# 100pqfpBreakout.net
KiCad netlist of a schematic drawn in EAGLE
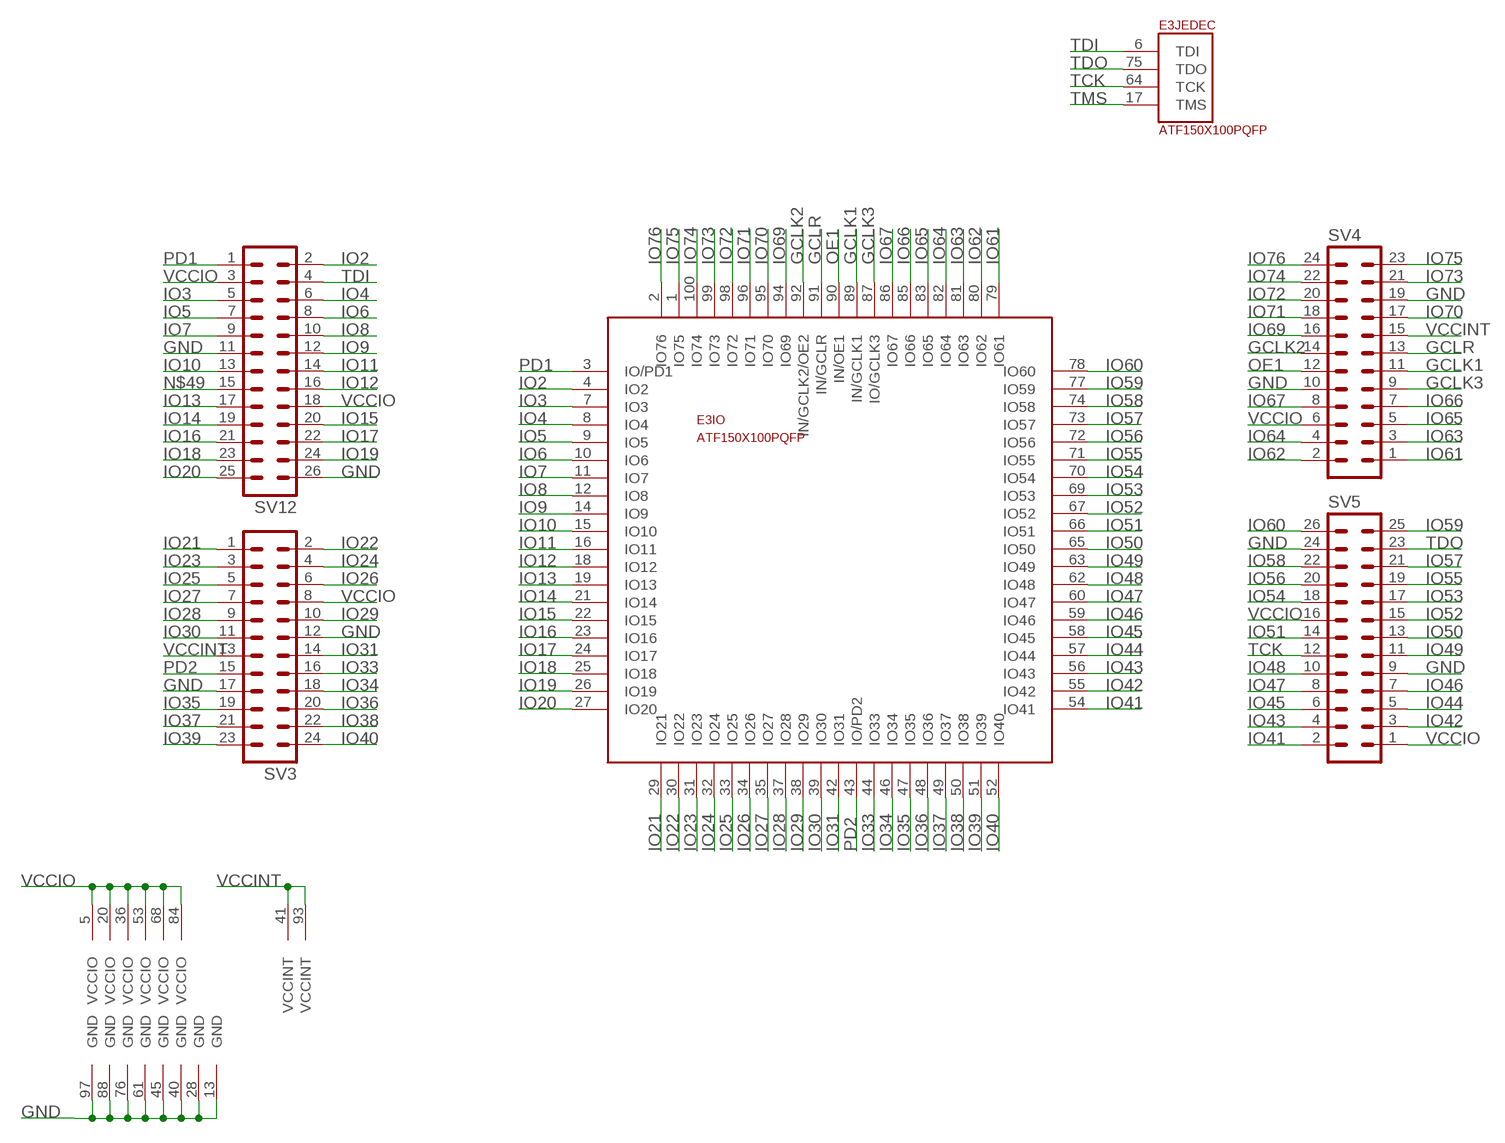
[diagram p0: schematic, sheet 1]

(export (version "E")
  (design (tool "Eeschema 10.0.6"))
  (components
    (comp (ref "E3")
      (value "ATF150X100PQFP")
      (footprint "eagle-import:PQFP-100")
      (libsource (lib "eagle-import") (part "ATF150X100PQFP"))
    )
    (comp (ref "SV3")
      (value "MA12-2")
      (footprint "eagle-import:MA12-2")
      (libsource (lib "eagle-import") (part "MA12-2"))
    )
    (comp (ref "SV4")
      (value "MA12-2")
      (footprint "eagle-import:MA12-2")
      (libsource (lib "eagle-import") (part "MA12-2"))
    )
    (comp (ref "SV5")
      (value "MA13-2")
      (footprint "eagle-import:MA13-2")
      (libsource (lib "eagle-import") (part "MA13-2"))
    )
    (comp (ref "SV12")
      (value "MA13-2")
      (footprint "eagle-import:MA13-2")
      (libsource (lib "eagle-import") (part "MA13-2"))
    )
  )
  (nets
    (net (code "1") (name "/GCLK1") (class "Default")
      (node (ref "E3") (pin "89") (pinfunction "IN/GCLK1_89") (pintype "input"))
      (node (ref "SV4") (pin "11") (pinfunction "11_11") (pintype "passive"))
    )
    (net (code "2") (name "/GCLK2") (class "Default")
      (node (ref "E3") (pin "92") (pinfunction "IN/GCLK2/OE2_92") (pintype "input"))
      (node (ref "SV4") (pin "14") (pinfunction "14_14") (pintype "passive"))
    )
    (net (code "3") (name "/GCLK3") (class "Default")
      (node (ref "E3") (pin "87") (pinfunction "IO/GCLK3_87") (pintype "bidirectional"))
      (node (ref "SV4") (pin "9") (pinfunction "9_9") (pintype "passive"))
    )
    (net (code "4") (name "/GCLR") (class "Default")
      (node (ref "E3") (pin "91") (pinfunction "IN/GCLR_91") (pintype "input"))
      (node (ref "SV4") (pin "13") (pinfunction "13_13") (pintype "passive"))
    )
    (net (code "5") (name "/GND") (class "Default")
      (node (ref "E3") (pin "13") (pinfunction "GND_13") (pintype "power_in"))
      (node (ref "E3") (pin "28") (pinfunction "GND_28") (pintype "power_in"))
      (node (ref "E3") (pin "40") (pinfunction "GND_40") (pintype "power_in"))
      (node (ref "E3") (pin "45") (pinfunction "GND_45") (pintype "power_in"))
      (node (ref "E3") (pin "61") (pinfunction "GND_61") (pintype "power_in"))
      (node (ref "E3") (pin "76") (pinfunction "GND_76") (pintype "power_in"))
      (node (ref "E3") (pin "88") (pinfunction "GND_88") (pintype "power_in"))
      (node (ref "E3") (pin "97") (pinfunction "GND_97") (pintype "power_in"))
      (node (ref "SV12") (pin "11") (pinfunction "11_11") (pintype "passive"))
      (node (ref "SV12") (pin "26") (pinfunction "26_26") (pintype "passive"))
      (node (ref "SV3") (pin "12") (pinfunction "12_12") (pintype "passive"))
      (node (ref "SV3") (pin "17") (pinfunction "17_17") (pintype "passive"))
      (node (ref "SV4") (pin "10") (pinfunction "10_10") (pintype "passive"))
      (node (ref "SV4") (pin "19") (pinfunction "19_19") (pintype "passive"))
      (node (ref "SV5") (pin "24") (pinfunction "24_24") (pintype "passive"))
      (node (ref "SV5") (pin "9") (pinfunction "9_9") (pintype "passive"))
    )
    (net (code "6") (name "/IO2") (class "Default")
      (node (ref "E3") (pin "4") (pinfunction "IO2_4") (pintype "bidirectional"))
      (node (ref "SV12") (pin "2") (pinfunction "2_2") (pintype "passive"))
    )
    (net (code "7") (name "/IO3") (class "Default")
      (node (ref "E3") (pin "7") (pinfunction "IO3_7") (pintype "bidirectional"))
      (node (ref "SV12") (pin "5") (pinfunction "5_5") (pintype "passive"))
    )
    (net (code "8") (name "/IO4") (class "Default")
      (node (ref "E3") (pin "8") (pinfunction "IO4_8") (pintype "bidirectional"))
      (node (ref "SV12") (pin "6") (pinfunction "6_6") (pintype "passive"))
    )
    (net (code "9") (name "/IO5") (class "Default")
      (node (ref "E3") (pin "9") (pinfunction "IO5_9") (pintype "bidirectional"))
      (node (ref "SV12") (pin "7") (pinfunction "7_7") (pintype "passive"))
    )
    (net (code "10") (name "/IO6") (class "Default")
      (node (ref "E3") (pin "10") (pinfunction "IO6_10") (pintype "bidirectional"))
      (node (ref "SV12") (pin "8") (pinfunction "8_8") (pintype "passive"))
    )
    (net (code "11") (name "/IO7") (class "Default")
      (node (ref "E3") (pin "11") (pinfunction "IO7_11") (pintype "bidirectional"))
      (node (ref "SV12") (pin "9") (pinfunction "9_9") (pintype "passive"))
    )
    (net (code "12") (name "/IO8") (class "Default")
      (node (ref "E3") (pin "12") (pinfunction "IO8_12") (pintype "bidirectional"))
      (node (ref "SV12") (pin "10") (pinfunction "10_10") (pintype "passive"))
    )
    (net (code "13") (name "/IO9") (class "Default")
      (node (ref "E3") (pin "14") (pinfunction "IO9_14") (pintype "bidirectional"))
      (node (ref "SV12") (pin "12") (pinfunction "12_12") (pintype "passive"))
    )
    (net (code "14") (name "/IO10") (class "Default")
      (node (ref "E3") (pin "15") (pinfunction "IO10_15") (pintype "bidirectional"))
      (node (ref "SV12") (pin "13") (pinfunction "13_13") (pintype "passive"))
    )
    (net (code "15") (name "/IO11") (class "Default")
      (node (ref "E3") (pin "16") (pinfunction "IO11_16") (pintype "bidirectional"))
      (node (ref "SV12") (pin "14") (pinfunction "14_14") (pintype "passive"))
    )
    (net (code "16") (name "/IO12") (class "Default")
      (node (ref "E3") (pin "18") (pinfunction "IO12_18") (pintype "bidirectional"))
      (node (ref "SV12") (pin "16") (pinfunction "16_16") (pintype "passive"))
    )
    (net (code "17") (name "/IO13") (class "Default")
      (node (ref "E3") (pin "19") (pinfunction "IO13_19") (pintype "bidirectional"))
      (node (ref "SV12") (pin "17") (pinfunction "17_17") (pintype "passive"))
    )
    (net (code "18") (name "/IO14") (class "Default")
      (node (ref "E3") (pin "21") (pinfunction "IO14_21") (pintype "bidirectional"))
      (node (ref "SV12") (pin "19") (pinfunction "19_19") (pintype "passive"))
    )
    (net (code "19") (name "/IO15") (class "Default")
      (node (ref "E3") (pin "22") (pinfunction "IO15_22") (pintype "bidirectional"))
      (node (ref "SV12") (pin "20") (pinfunction "20_20") (pintype "passive"))
    )
    (net (code "20") (name "/IO16") (class "Default")
      (node (ref "E3") (pin "23") (pinfunction "IO16_23") (pintype "bidirectional"))
      (node (ref "SV12") (pin "21") (pinfunction "21_21") (pintype "passive"))
    )
    (net (code "21") (name "/IO17") (class "Default")
      (node (ref "E3") (pin "24") (pinfunction "IO17_24") (pintype "bidirectional"))
      (node (ref "SV12") (pin "22") (pinfunction "22_22") (pintype "passive"))
    )
    (net (code "22") (name "/IO18") (class "Default")
      (node (ref "E3") (pin "25") (pinfunction "IO18_25") (pintype "bidirectional"))
      (node (ref "SV12") (pin "23") (pinfunction "23_23") (pintype "passive"))
    )
    (net (code "23") (name "/IO19") (class "Default")
      (node (ref "E3") (pin "26") (pinfunction "IO19_26") (pintype "bidirectional"))
      (node (ref "SV12") (pin "24") (pinfunction "24_24") (pintype "passive"))
    )
    (net (code "24") (name "/IO20") (class "Default")
      (node (ref "E3") (pin "27") (pinfunction "IO20_27") (pintype "bidirectional"))
      (node (ref "SV12") (pin "25") (pinfunction "25_25") (pintype "passive"))
    )
    (net (code "25") (name "/IO21") (class "Default")
      (node (ref "E3") (pin "29") (pinfunction "IO21_29") (pintype "bidirectional"))
      (node (ref "SV3") (pin "1") (pinfunction "1_1") (pintype "passive"))
    )
    (net (code "26") (name "/IO22") (class "Default")
      (node (ref "E3") (pin "30") (pinfunction "IO22_30") (pintype "bidirectional"))
      (node (ref "SV3") (pin "2") (pinfunction "2_2") (pintype "passive"))
    )
    (net (code "27") (name "/IO23") (class "Default")
      (node (ref "E3") (pin "31") (pinfunction "IO23_31") (pintype "bidirectional"))
      (node (ref "SV3") (pin "3") (pinfunction "3_3") (pintype "passive"))
    )
    (net (code "28") (name "/IO24") (class "Default")
      (node (ref "E3") (pin "32") (pinfunction "IO24_32") (pintype "bidirectional"))
      (node (ref "SV3") (pin "4") (pinfunction "4_4") (pintype "passive"))
    )
    (net (code "29") (name "/IO25") (class "Default")
      (node (ref "E3") (pin "33") (pinfunction "IO25_33") (pintype "bidirectional"))
      (node (ref "SV3") (pin "5") (pinfunction "5_5") (pintype "passive"))
    )
    (net (code "30") (name "/IO26") (class "Default")
      (node (ref "E3") (pin "34") (pinfunction "IO26_34") (pintype "bidirectional"))
      (node (ref "SV3") (pin "6") (pinfunction "6_6") (pintype "passive"))
    )
    (net (code "31") (name "/IO27") (class "Default")
      (node (ref "E3") (pin "35") (pinfunction "IO27_35") (pintype "bidirectional"))
      (node (ref "SV3") (pin "7") (pinfunction "7_7") (pintype "passive"))
    )
    (net (code "32") (name "/IO28") (class "Default")
      (node (ref "E3") (pin "37") (pinfunction "IO28_37") (pintype "bidirectional"))
      (node (ref "SV3") (pin "9") (pinfunction "9_9") (pintype "passive"))
    )
    (net (code "33") (name "/IO29") (class "Default")
      (node (ref "E3") (pin "38") (pinfunction "IO29_38") (pintype "bidirectional"))
      (node (ref "SV3") (pin "10") (pinfunction "10_10") (pintype "passive"))
    )
    (net (code "34") (name "/IO30") (class "Default")
      (node (ref "E3") (pin "39") (pinfunction "IO30_39") (pintype "bidirectional"))
      (node (ref "SV3") (pin "11") (pinfunction "11_11") (pintype "passive"))
    )
    (net (code "35") (name "/IO31") (class "Default")
      (node (ref "E3") (pin "42") (pinfunction "IO31_42") (pintype "bidirectional"))
      (node (ref "SV3") (pin "14") (pinfunction "14_14") (pintype "passive"))
    )
    (net (code "36") (name "/IO33") (class "Default")
      (node (ref "E3") (pin "44") (pinfunction "IO33_44") (pintype "bidirectional"))
      (node (ref "SV3") (pin "16") (pinfunction "16_16") (pintype "passive"))
    )
    (net (code "37") (name "/IO34") (class "Default")
      (node (ref "E3") (pin "46") (pinfunction "IO34_46") (pintype "bidirectional"))
      (node (ref "SV3") (pin "18") (pinfunction "18_18") (pintype "passive"))
    )
    (net (code "38") (name "/IO35") (class "Default")
      (node (ref "E3") (pin "47") (pinfunction "IO35_47") (pintype "bidirectional"))
      (node (ref "SV3") (pin "19") (pinfunction "19_19") (pintype "passive"))
    )
    (net (code "39") (name "/IO36") (class "Default")
      (node (ref "E3") (pin "48") (pinfunction "IO36_48") (pintype "bidirectional"))
      (node (ref "SV3") (pin "20") (pinfunction "20_20") (pintype "passive"))
    )
    (net (code "40") (name "/IO37") (class "Default")
      (node (ref "E3") (pin "49") (pinfunction "IO37_49") (pintype "bidirectional"))
      (node (ref "SV3") (pin "21") (pinfunction "21_21") (pintype "passive"))
    )
    (net (code "41") (name "/IO38") (class "Default")
      (node (ref "E3") (pin "50") (pinfunction "IO38_50") (pintype "bidirectional"))
      (node (ref "SV3") (pin "22") (pinfunction "22_22") (pintype "passive"))
    )
    (net (code "42") (name "/IO39") (class "Default")
      (node (ref "E3") (pin "51") (pinfunction "IO39_51") (pintype "bidirectional"))
      (node (ref "SV3") (pin "23") (pinfunction "23_23") (pintype "passive"))
    )
    (net (code "43") (name "/IO40") (class "Default")
      (node (ref "E3") (pin "52") (pinfunction "IO40_52") (pintype "bidirectional"))
      (node (ref "SV3") (pin "24") (pinfunction "24_24") (pintype "passive"))
    )
    (net (code "44") (name "/IO41") (class "Default")
      (node (ref "E3") (pin "54") (pinfunction "IO41_54") (pintype "bidirectional"))
      (node (ref "SV5") (pin "2") (pinfunction "2_2") (pintype "passive"))
    )
    (net (code "45") (name "/IO42") (class "Default")
      (node (ref "E3") (pin "55") (pinfunction "IO42_55") (pintype "bidirectional"))
      (node (ref "SV5") (pin "3") (pinfunction "3_3") (pintype "passive"))
    )
    (net (code "46") (name "/IO43") (class "Default")
      (node (ref "E3") (pin "56") (pinfunction "IO43_56") (pintype "bidirectional"))
      (node (ref "SV5") (pin "4") (pinfunction "4_4") (pintype "passive"))
    )
    (net (code "47") (name "/IO44") (class "Default")
      (node (ref "E3") (pin "57") (pinfunction "IO44_57") (pintype "bidirectional"))
      (node (ref "SV5") (pin "5") (pinfunction "5_5") (pintype "passive"))
    )
    (net (code "48") (name "/IO45") (class "Default")
      (node (ref "E3") (pin "58") (pinfunction "IO45_58") (pintype "bidirectional"))
      (node (ref "SV5") (pin "6") (pinfunction "6_6") (pintype "passive"))
    )
    (net (code "49") (name "/IO46") (class "Default")
      (node (ref "E3") (pin "59") (pinfunction "IO46_59") (pintype "bidirectional"))
      (node (ref "SV5") (pin "7") (pinfunction "7_7") (pintype "passive"))
    )
    (net (code "50") (name "/IO47") (class "Default")
      (node (ref "E3") (pin "60") (pinfunction "IO47_60") (pintype "bidirectional"))
      (node (ref "SV5") (pin "8") (pinfunction "8_8") (pintype "passive"))
    )
    (net (code "51") (name "/IO48") (class "Default")
      (node (ref "E3") (pin "62") (pinfunction "IO48_62") (pintype "bidirectional"))
      (node (ref "SV5") (pin "10") (pinfunction "10_10") (pintype "passive"))
    )
    (net (code "52") (name "/IO49") (class "Default")
      (node (ref "E3") (pin "63") (pinfunction "IO49_63") (pintype "bidirectional"))
      (node (ref "SV5") (pin "11") (pinfunction "11_11") (pintype "passive"))
    )
    (net (code "53") (name "/IO50") (class "Default")
      (node (ref "E3") (pin "65") (pinfunction "IO50_65") (pintype "bidirectional"))
      (node (ref "SV5") (pin "13") (pinfunction "13_13") (pintype "passive"))
    )
    (net (code "54") (name "/IO51") (class "Default")
      (node (ref "E3") (pin "66") (pinfunction "IO51_66") (pintype "bidirectional"))
      (node (ref "SV5") (pin "14") (pinfunction "14_14") (pintype "passive"))
    )
    (net (code "55") (name "/IO52") (class "Default")
      (node (ref "E3") (pin "67") (pinfunction "IO52_67") (pintype "bidirectional"))
      (node (ref "SV5") (pin "15") (pinfunction "15_15") (pintype "passive"))
    )
    (net (code "56") (name "/IO53") (class "Default")
      (node (ref "E3") (pin "69") (pinfunction "IO53_69") (pintype "bidirectional"))
      (node (ref "SV5") (pin "17") (pinfunction "17_17") (pintype "passive"))
    )
    (net (code "57") (name "/IO54") (class "Default")
      (node (ref "E3") (pin "70") (pinfunction "IO54_70") (pintype "bidirectional"))
      (node (ref "SV5") (pin "18") (pinfunction "18_18") (pintype "passive"))
    )
    (net (code "58") (name "/IO55") (class "Default")
      (node (ref "E3") (pin "71") (pinfunction "IO55_71") (pintype "bidirectional"))
      (node (ref "SV5") (pin "19") (pinfunction "19_19") (pintype "passive"))
    )
    (net (code "59") (name "/IO56") (class "Default")
      (node (ref "E3") (pin "72") (pinfunction "IO56_72") (pintype "bidirectional"))
      (node (ref "SV5") (pin "20") (pinfunction "20_20") (pintype "passive"))
    )
    (net (code "60") (name "/IO57") (class "Default")
      (node (ref "E3") (pin "73") (pinfunction "IO57_73") (pintype "bidirectional"))
      (node (ref "SV5") (pin "21") (pinfunction "21_21") (pintype "passive"))
    )
    (net (code "61") (name "/IO58") (class "Default")
      (node (ref "E3") (pin "74") (pinfunction "IO58_74") (pintype "bidirectional"))
      (node (ref "SV5") (pin "22") (pinfunction "22_22") (pintype "passive"))
    )
    (net (code "62") (name "/IO59") (class "Default")
      (node (ref "E3") (pin "77") (pinfunction "IO59_77") (pintype "bidirectional"))
      (node (ref "SV5") (pin "25") (pinfunction "25_25") (pintype "passive"))
    )
    (net (code "63") (name "/IO60") (class "Default")
      (node (ref "E3") (pin "78") (pinfunction "IO60_78") (pintype "bidirectional"))
      (node (ref "SV5") (pin "26") (pinfunction "26_26") (pintype "passive"))
    )
    (net (code "64") (name "/IO61") (class "Default")
      (node (ref "E3") (pin "79") (pinfunction "IO61_79") (pintype "bidirectional"))
      (node (ref "SV4") (pin "1") (pinfunction "1_1") (pintype "passive"))
    )
    (net (code "65") (name "/IO62") (class "Default")
      (node (ref "E3") (pin "80") (pinfunction "IO62_80") (pintype "bidirectional"))
      (node (ref "SV4") (pin "2") (pinfunction "2_2") (pintype "passive"))
    )
    (net (code "66") (name "/IO63") (class "Default")
      (node (ref "E3") (pin "81") (pinfunction "IO63_81") (pintype "bidirectional"))
      (node (ref "SV4") (pin "3") (pinfunction "3_3") (pintype "passive"))
    )
    (net (code "67") (name "/IO64") (class "Default")
      (node (ref "E3") (pin "82") (pinfunction "IO64_82") (pintype "bidirectional"))
      (node (ref "SV4") (pin "4") (pinfunction "4_4") (pintype "passive"))
    )
    (net (code "68") (name "/IO65") (class "Default")
      (node (ref "E3") (pin "83") (pinfunction "IO65_83") (pintype "bidirectional"))
      (node (ref "SV4") (pin "5") (pinfunction "5_5") (pintype "passive"))
    )
    (net (code "69") (name "/IO66") (class "Default")
      (node (ref "E3") (pin "85") (pinfunction "IO66_85") (pintype "bidirectional"))
      (node (ref "SV4") (pin "7") (pinfunction "7_7") (pintype "passive"))
    )
    (net (code "70") (name "/IO67") (class "Default")
      (node (ref "E3") (pin "86") (pinfunction "IO67_86") (pintype "bidirectional"))
      (node (ref "SV4") (pin "8") (pinfunction "8_8") (pintype "passive"))
    )
    (net (code "71") (name "/IO69") (class "Default")
      (node (ref "E3") (pin "94") (pinfunction "IO69_94") (pintype "bidirectional"))
      (node (ref "SV4") (pin "16") (pinfunction "16_16") (pintype "passive"))
    )
    (net (code "72") (name "/IO70") (class "Default")
      (node (ref "E3") (pin "95") (pinfunction "IO70_95") (pintype "bidirectional"))
      (node (ref "SV4") (pin "17") (pinfunction "17_17") (pintype "passive"))
    )
    (net (code "73") (name "/IO71") (class "Default")
      (node (ref "E3") (pin "96") (pinfunction "IO71_96") (pintype "bidirectional"))
      (node (ref "SV4") (pin "18") (pinfunction "18_18") (pintype "passive"))
    )
    (net (code "74") (name "/IO72") (class "Default")
      (node (ref "E3") (pin "98") (pinfunction "IO72_98") (pintype "bidirectional"))
      (node (ref "SV4") (pin "20") (pinfunction "20_20") (pintype "passive"))
    )
    (net (code "75") (name "/IO73") (class "Default")
      (node (ref "E3") (pin "99") (pinfunction "IO73_99") (pintype "bidirectional"))
      (node (ref "SV4") (pin "21") (pinfunction "21_21") (pintype "passive"))
    )
    (net (code "76") (name "/IO74") (class "Default")
      (node (ref "E3") (pin "100") (pinfunction "IO74_100") (pintype "bidirectional"))
      (node (ref "SV4") (pin "22") (pinfunction "22_22") (pintype "passive"))
    )
    (net (code "77") (name "/IO75") (class "Default")
      (node (ref "E3") (pin "1") (pinfunction "IO75_1") (pintype "bidirectional"))
      (node (ref "SV4") (pin "23") (pinfunction "23_23") (pintype "passive"))
    )
    (net (code "78") (name "/IO76") (class "Default")
      (node (ref "E3") (pin "2") (pinfunction "IO76_2") (pintype "bidirectional"))
      (node (ref "SV4") (pin "24") (pinfunction "24_24") (pintype "passive"))
    )
    (net (code "79") (name "/N$49") (class "Default")
      (node (ref "SV12") (pin "15") (pinfunction "15_15") (pintype "passive"))
    )
    (net (code "80") (name "/OE1") (class "Default")
      (node (ref "E3") (pin "90") (pinfunction "IN/OE1_90") (pintype "input"))
      (node (ref "SV4") (pin "12") (pinfunction "12_12") (pintype "passive"))
    )
    (net (code "81") (name "/PD1") (class "Default")
      (node (ref "E3") (pin "3") (pinfunction "IO/PD1_3") (pintype "bidirectional"))
      (node (ref "SV12") (pin "1") (pinfunction "1_1") (pintype "passive"))
    )
    (net (code "82") (name "/PD2") (class "Default")
      (node (ref "E3") (pin "43") (pinfunction "IO/PD2_43") (pintype "bidirectional"))
      (node (ref "SV3") (pin "15") (pinfunction "15_15") (pintype "passive"))
    )
    (net (code "83") (name "/TCK") (class "Default")
      (node (ref "E3") (pin "64") (pinfunction "TCK_64") (pintype "bidirectional"))
      (node (ref "SV5") (pin "12") (pinfunction "12_12") (pintype "passive"))
    )
    (net (code "84") (name "/TDI") (class "Default")
      (node (ref "E3") (pin "6") (pinfunction "TDI_6") (pintype "bidirectional"))
      (node (ref "SV12") (pin "4") (pinfunction "4_4") (pintype "passive"))
    )
    (net (code "85") (name "/TDO") (class "Default")
      (node (ref "E3") (pin "75") (pinfunction "TDO_75") (pintype "bidirectional"))
      (node (ref "SV5") (pin "23") (pinfunction "23_23") (pintype "passive"))
    )
    (net (code "86") (name "/TMS") (class "Default")
      (node (ref "E3") (pin "17") (pinfunction "TMS_17") (pintype "bidirectional"))
    )
    (net (code "87") (name "/VCCINT") (class "Default")
      (node (ref "E3") (pin "41") (pinfunction "VCCINT_41") (pintype "power_in"))
      (node (ref "E3") (pin "93") (pinfunction "VCCINT_93") (pintype "power_in"))
      (node (ref "SV3") (pin "13") (pinfunction "13_13") (pintype "passive"))
      (node (ref "SV4") (pin "15") (pinfunction "15_15") (pintype "passive"))
    )
    (net (code "88") (name "/VCCIO") (class "Default")
      (node (ref "E3") (pin "20") (pinfunction "VCCIO_20") (pintype "power_in"))
      (node (ref "E3") (pin "36") (pinfunction "VCCIO_36") (pintype "power_in"))
      (node (ref "E3") (pin "5") (pinfunction "VCCIO_5") (pintype "power_in"))
      (node (ref "E3") (pin "53") (pinfunction "VCCIO_53") (pintype "power_in"))
      (node (ref "E3") (pin "68") (pinfunction "VCCIO_68") (pintype "power_in"))
      (node (ref "E3") (pin "84") (pinfunction "VCCIO_84") (pintype "power_in"))
      (node (ref "SV12") (pin "18") (pinfunction "18_18") (pintype "passive"))
      (node (ref "SV12") (pin "3") (pinfunction "3_3") (pintype "passive"))
      (node (ref "SV3") (pin "8") (pinfunction "8_8") (pintype "passive"))
      (node (ref "SV4") (pin "6") (pinfunction "6_6") (pintype "passive"))
      (node (ref "SV5") (pin "1") (pinfunction "1_1") (pintype "passive"))
      (node (ref "SV5") (pin "16") (pinfunction "16_16") (pintype "passive"))
    )
  )
)
